# 6.net
KiCad netlist of a schematic drawn in Altium Designer
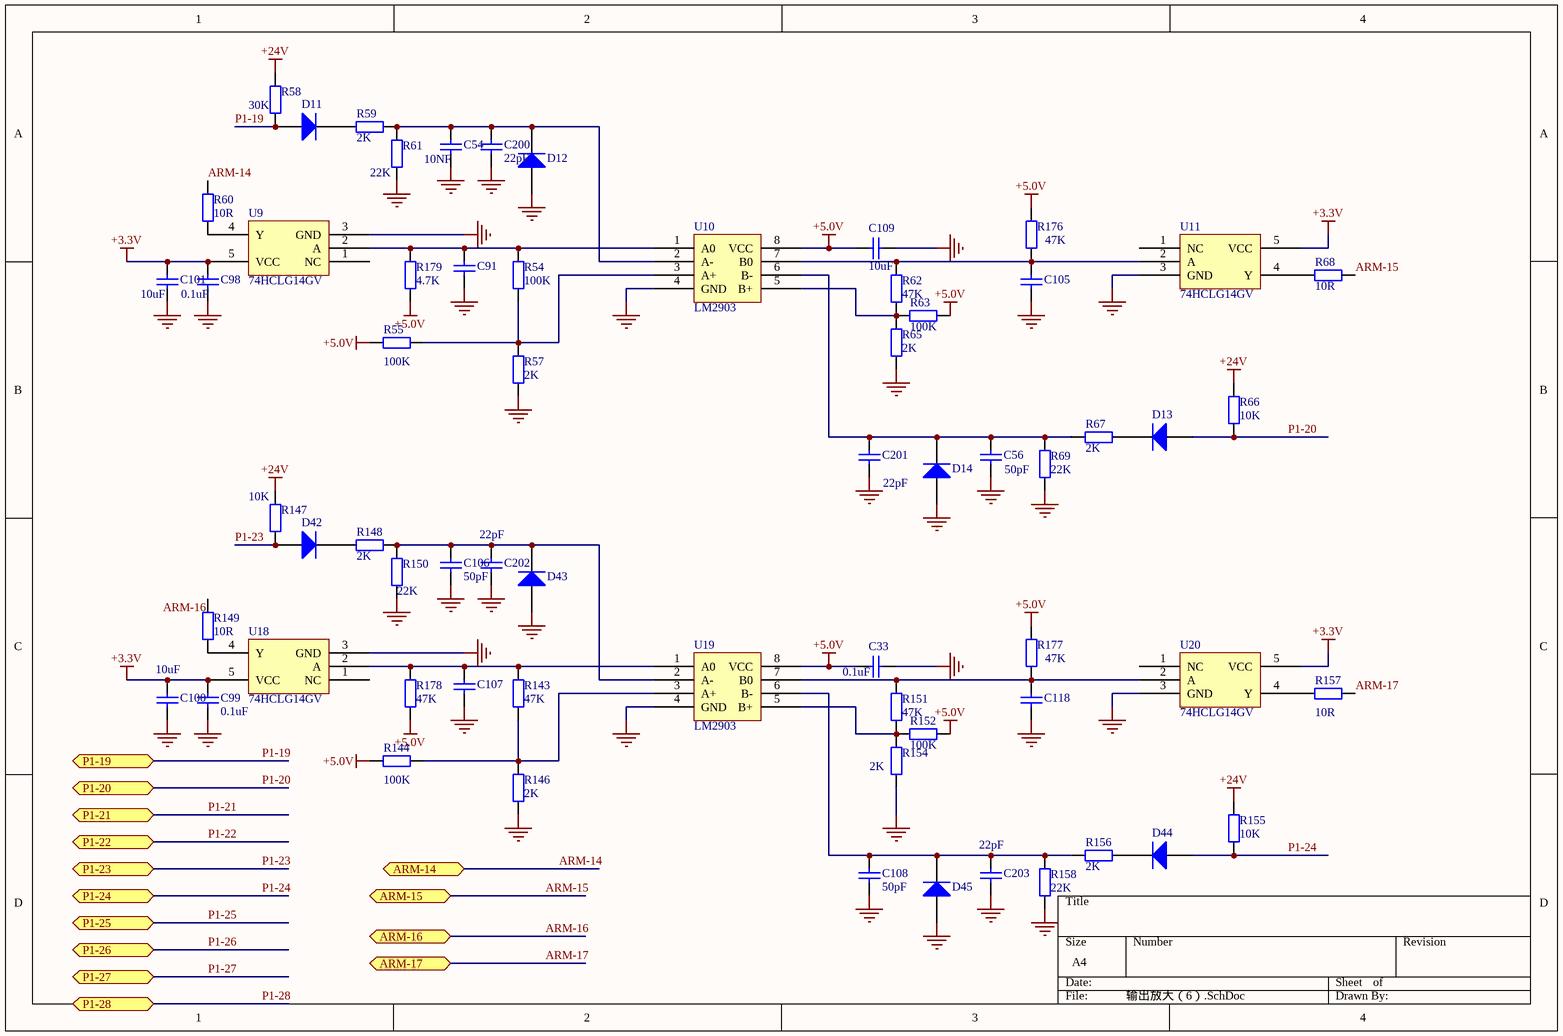
[diagram p0: 输出放大（6）.SchDoc]

(export (version "E")
  (design (tool "Eeschema 10.0.6"))
  (components
    (comp (ref "C33")
      (value "0.1uF")
      (footprint "采集板3.0增加1路模拟量2:C0805")
      (description "Capacitor")
      (fields (field (name "Comment") "Cap") (field (name "PUBLISHER") "Altium Limited"))
      (libsource (lib "Miscellaneous Devices") (part "Cap"))
    )
    (comp (ref "C54")
      (value "10NF")
      (footprint "C0805")
      (description "Capacitor")
      (fields (field (name "Comment") "Cap") (field (name "PUBLISHER") "Altium Limited"))
      (libsource (lib "Miscellaneous Devices") (part "Cap"))
    )
    (comp (ref "C56")
      (value "50pF")
      (footprint "C0805")
      (description "Capacitor")
      (fields (field (name "Comment") "Cap") (field (name "PUBLISHER") "Altium Limited"))
      (libsource (lib "Miscellaneous Devices") (part "Cap"))
    )
    (comp (ref "C91")
      (value "Cap")
      (footprint "C0805")
      (description "Capacitor")
      (fields (field (name "PUBLISHER") "Altium Limited"))
      (libsource (lib "Miscellaneous Devices") (part "Cap"))
    )
    (comp (ref "C98")
      (value "0.1uF")
      (footprint "采集板3.0增加1路模拟量2:C0805")
      (description "Capacitor")
      (fields (field (name "Comment") "Cap") (field (name "PUBLISHER") "Altium Limited"))
      (libsource (lib "Miscellaneous Devices") (part "Cap"))
    )
    (comp (ref "C99")
      (value "0.1uF")
      (footprint "采集板3.0增加1路模拟量2:C0805")
      (description "Capacitor")
      (fields (field (name "Comment") "Cap") (field (name "PUBLISHER") "Altium Limited"))
      (libsource (lib "Miscellaneous Devices") (part "Cap"))
    )
    (comp (ref "C100")
      (value "10uF")
      (footprint "C1206")
      (description "Capacitor")
      (fields (field (name "Comment") "Cap") (field (name "PUBLISHER") "Altium Limited"))
      (libsource (lib "Miscellaneous Devices") (part "Cap"))
    )
    (comp (ref "C101")
      (value "10uF")
      (footprint "C1206")
      (description "Capacitor")
      (fields (field (name "Comment") "Cap") (field (name "PUBLISHER") "Altium Limited"))
      (libsource (lib "Miscellaneous Devices") (part "Cap"))
    )
    (comp (ref "C105")
      (value "Cap")
      (footprint "C0805")
      (description "Capacitor")
      (fields (field (name "PUBLISHER") "Altium Limited"))
      (libsource (lib "Miscellaneous Devices") (part "Cap"))
    )
    (comp (ref "C106")
      (value "50pF")
      (footprint "C0805")
      (description "Capacitor")
      (fields (field (name "Comment") "Cap") (field (name "PUBLISHER") "Altium Limited"))
      (libsource (lib "Miscellaneous Devices") (part "Cap"))
    )
    (comp (ref "C107")
      (value "Cap")
      (footprint "C0805")
      (description "Capacitor")
      (fields (field (name "PUBLISHER") "Altium Limited"))
      (libsource (lib "Miscellaneous Devices") (part "Cap"))
    )
    (comp (ref "C108")
      (value "50pF")
      (footprint "C0805")
      (description "Capacitor")
      (fields (field (name "Comment") "Cap") (field (name "PUBLISHER") "Altium Limited"))
      (libsource (lib "Miscellaneous Devices") (part "Cap"))
    )
    (comp (ref "C109")
      (value "10uF")
      (footprint "C1206")
      (description "Capacitor")
      (fields (field (name "Comment") "Cap") (field (name "PUBLISHER") "Altium Limited"))
      (libsource (lib "Miscellaneous Devices") (part "Cap"))
    )
    (comp (ref "C118")
      (value "Cap")
      (footprint "C0805")
      (description "Capacitor")
      (fields (field (name "PUBLISHER") "Altium Limited"))
      (libsource (lib "Miscellaneous Devices") (part "Cap"))
    )
    (comp (ref "C200")
      (value "22pF")
      (footprint "采集板3.0增加1路模拟量2:C0805")
      (description "Capacitor")
      (fields (field (name "Comment") "Cap") (field (name "PUBLISHER") "Altium Limited"))
      (libsource (lib "Miscellaneous Devices") (part "Cap"))
    )
    (comp (ref "C201")
      (value "22pF")
      (footprint "采集板3.0增加1路模拟量2:C0805")
      (description "Capacitor")
      (fields (field (name "Comment") "Cap") (field (name "PUBLISHER") "Altium Limited"))
      (libsource (lib "Miscellaneous Devices") (part "Cap"))
    )
    (comp (ref "C202")
      (value "22pF")
      (footprint "采集板3.0增加1路模拟量2:C0805")
      (description "Capacitor")
      (fields (field (name "Comment") "Cap") (field (name "PUBLISHER") "Altium Limited"))
      (libsource (lib "Miscellaneous Devices") (part "Cap"))
    )
    (comp (ref "C203")
      (value "22pF")
      (footprint "采集板3.0增加1路模拟量2:C0805")
      (description "Capacitor")
      (fields (field (name "Comment") "Cap") (field (name "PUBLISHER") "Altium Limited"))
      (libsource (lib "Miscellaneous Devices") (part "Cap"))
    )
    (comp (ref "D11")
      (value "Diode 1N4007")
      (footprint "SOD123")
      (description "1 Amp General Purpose Rectifier")
      (fields (field (name "PUBLISHER") "Altium Limited"))
      (libsource (lib "Miscellaneous Devices") (part "Diode 1N4007"))
    )
    (comp (ref "D12")
      (value "Diode 1N4007")
      (footprint "SOD123")
      (description "1 Amp General Purpose Rectifier")
      (fields (field (name "PUBLISHER") "Altium Limited"))
      (libsource (lib "Miscellaneous Devices") (part "Diode 1N4007"))
    )
    (comp (ref "D13")
      (value "Diode 1N4007")
      (footprint "SOD123")
      (description "1 Amp General Purpose Rectifier")
      (fields (field (name "PUBLISHER") "Altium Limited"))
      (libsource (lib "Miscellaneous Devices") (part "Diode 1N4007"))
    )
    (comp (ref "D14")
      (value "Diode 1N4007")
      (footprint "SOD123")
      (description "1 Amp General Purpose Rectifier")
      (fields (field (name "PUBLISHER") "Altium Limited"))
      (libsource (lib "Miscellaneous Devices") (part "Diode 1N4007"))
    )
    (comp (ref "D42")
      (value "Diode 1N4007")
      (footprint "SOD123")
      (description "1 Amp General Purpose Rectifier")
      (fields (field (name "PUBLISHER") "Altium Limited"))
      (libsource (lib "Miscellaneous Devices") (part "Diode 1N4007"))
    )
    (comp (ref "D43")
      (value "Diode 1N4007")
      (footprint "SOD123")
      (description "1 Amp General Purpose Rectifier")
      (fields (field (name "PUBLISHER") "Altium Limited"))
      (libsource (lib "Miscellaneous Devices") (part "Diode 1N4007"))
    )
    (comp (ref "D44")
      (value "Diode 1N4007")
      (footprint "SOD123")
      (description "1 Amp General Purpose Rectifier")
      (fields (field (name "PUBLISHER") "Altium Limited"))
      (libsource (lib "Miscellaneous Devices") (part "Diode 1N4007"))
    )
    (comp (ref "D45")
      (value "Diode 1N4007")
      (footprint "SOD123")
      (description "1 Amp General Purpose Rectifier")
      (fields (field (name "PUBLISHER") "Altium Limited"))
      (libsource (lib "Miscellaneous Devices") (part "Diode 1N4007"))
    )
    (comp (ref "R54")
      (value "100K")
      (footprint "采集板3.0增加1路模拟量2:R0805")
      (description "Resistor")
      (fields (field (name "Comment") "Res2") (field (name "PUBLISHER") "Altium Limited"))
      (libsource (lib "") (part "Res2_3"))
    )
    (comp (ref "R55")
      (value "100K")
      (footprint "采集板3.0增加1路模拟量2:R0805")
      (description "Resistor")
      (fields (field (name "Comment") "Res2") (field (name "PUBLISHER") "Altium Limited"))
      (libsource (lib "") (part "Res2_1"))
    )
    (comp (ref "R57")
      (value "2K")
      (footprint "采集板3.0增加1路模拟量2:R0805")
      (description "Resistor")
      (fields (field (name "Comment") "Res2") (field (name "PUBLISHER") "Altium Limited"))
      (libsource (lib "") (part "Res2_2"))
    )
    (comp (ref "R58")
      (value "30K")
      (footprint "采集板3.0增加1路模拟量2:R0805")
      (description "Resistor")
      (fields (field (name "Comment") "Res2") (field (name "PUBLISHER") "Altium Limited"))
      (libsource (lib "") (part "Res2_2"))
    )
    (comp (ref "R59")
      (value "2K")
      (footprint "采集板3.0增加1路模拟量2:R0805")
      (description "Resistor")
      (fields (field (name "Comment") "Res2") (field (name "PUBLISHER") "Altium Limited"))
      (libsource (lib "Miscellaneous Devices") (part "Res2"))
    )
    (comp (ref "R60")
      (value "10R")
      (footprint "采集板3.0增加1路模拟量2:R0805")
      (description "Resistor")
      (fields (field (name "Comment") "Res2") (field (name "PUBLISHER") "Altium Limited"))
      (libsource (lib "") (part "Res2_3"))
    )
    (comp (ref "R61")
      (value "22K")
      (footprint "采集板3.0增加1路模拟量2:R0805")
      (description "Resistor")
      (fields (field (name "Comment") "Res2") (field (name "PUBLISHER") "Altium Limited"))
      (libsource (lib "") (part "Res2_2"))
    )
    (comp (ref "R62")
      (value "47K")
      (footprint "采集板3.0增加1路模拟量2:R0805")
      (description "Resistor")
      (fields (field (name "Comment") "Res2") (field (name "PUBLISHER") "Altium Limited"))
      (libsource (lib "") (part "Res2_2"))
    )
    (comp (ref "R63")
      (value "100K")
      (footprint "采集板3.0增加1路模拟量2:R0805")
      (description "Resistor")
      (fields (field (name "Comment") "Res2") (field (name "PUBLISHER") "Altium Limited"))
      (libsource (lib "Miscellaneous Devices") (part "Res2"))
    )
    (comp (ref "R65")
      (value "2K")
      (footprint "采集板3.0增加1路模拟量2:R0805")
      (description "Resistor")
      (fields (field (name "Comment") "Res2") (field (name "PUBLISHER") "Altium Limited"))
      (libsource (lib "") (part "Res2_2"))
    )
    (comp (ref "R66")
      (value "10K")
      (footprint "采集板3.0增加1路模拟量2:R0805")
      (description "Resistor")
      (fields (field (name "Comment") "Res2") (field (name "PUBLISHER") "Altium Limited"))
      (libsource (lib "") (part "Res2_3"))
    )
    (comp (ref "R67")
      (value "2K")
      (footprint "采集板3.0增加1路模拟量2:R0805")
      (description "Resistor")
      (fields (field (name "Comment") "Res2") (field (name "PUBLISHER") "Altium Limited"))
      (libsource (lib "Miscellaneous Devices") (part "Res2"))
    )
    (comp (ref "R68")
      (value "10R")
      (footprint "采集板3.0增加1路模拟量2:R0805")
      (description "Resistor")
      (fields (field (name "Comment") "Res2") (field (name "PUBLISHER") "Altium Limited"))
      (libsource (lib "") (part "Res2_1"))
    )
    (comp (ref "R69")
      (value "22K")
      (footprint "采集板3.0增加1路模拟量2:R0805")
      (description "Resistor")
      (fields (field (name "Comment") "Res2") (field (name "PUBLISHER") "Altium Limited"))
      (libsource (lib "") (part "Res2_3"))
    )
    (comp (ref "R143")
      (value "47K")
      (footprint "采集板3.0增加1路模拟量2:R0805")
      (description "Resistor")
      (fields (field (name "Comment") "Res2") (field (name "PUBLISHER") "Altium Limited"))
      (libsource (lib "") (part "Res2_3"))
    )
    (comp (ref "R144")
      (value "100K")
      (footprint "采集板3.0增加1路模拟量2:R0805")
      (description "Resistor")
      (fields (field (name "Comment") "Res2") (field (name "PUBLISHER") "Altium Limited"))
      (libsource (lib "") (part "Res2_1"))
    )
    (comp (ref "R146")
      (value "2K")
      (footprint "采集板3.0增加1路模拟量2:R0805")
      (description "Resistor")
      (fields (field (name "Comment") "Res2") (field (name "PUBLISHER") "Altium Limited"))
      (libsource (lib "") (part "Res2_2"))
    )
    (comp (ref "R147")
      (value "10K")
      (footprint "采集板3.0增加1路模拟量2:R0805")
      (description "Resistor")
      (fields (field (name "Comment") "Res2") (field (name "PUBLISHER") "Altium Limited"))
      (libsource (lib "") (part "Res2_2"))
    )
    (comp (ref "R148")
      (value "2K")
      (footprint "采集板3.0增加1路模拟量2:R0805")
      (description "Resistor")
      (fields (field (name "Comment") "Res2") (field (name "PUBLISHER") "Altium Limited"))
      (libsource (lib "Miscellaneous Devices") (part "Res2"))
    )
    (comp (ref "R149")
      (value "10R")
      (footprint "采集板3.0增加1路模拟量2:R0805")
      (description "Resistor")
      (fields (field (name "Comment") "Res2") (field (name "PUBLISHER") "Altium Limited"))
      (libsource (lib "") (part "Res2_3"))
    )
    (comp (ref "R150")
      (value "22K")
      (footprint "采集板3.0增加1路模拟量2:R0805")
      (description "Resistor")
      (fields (field (name "Comment") "Res2") (field (name "PUBLISHER") "Altium Limited"))
      (libsource (lib "") (part "Res2_2"))
    )
    (comp (ref "R151")
      (value "47K")
      (footprint "采集板3.0增加1路模拟量2:R0805")
      (description "Resistor")
      (fields (field (name "Comment") "Res2") (field (name "PUBLISHER") "Altium Limited"))
      (libsource (lib "") (part "Res2_2"))
    )
    (comp (ref "R152")
      (value "100K")
      (footprint "采集板3.0增加1路模拟量2:R0805")
      (description "Resistor")
      (fields (field (name "Comment") "Res2") (field (name "PUBLISHER") "Altium Limited"))
      (libsource (lib "Miscellaneous Devices") (part "Res2"))
    )
    (comp (ref "R154")
      (value "2K")
      (footprint "采集板3.0增加1路模拟量2:R0805")
      (description "Resistor")
      (fields (field (name "Comment") "Res2") (field (name "PUBLISHER") "Altium Limited"))
      (libsource (lib "") (part "Res2_3"))
    )
    (comp (ref "R155")
      (value "10K")
      (footprint "采集板3.0增加1路模拟量2:R0805")
      (description "Resistor")
      (fields (field (name "Comment") "Res2") (field (name "PUBLISHER") "Altium Limited"))
      (libsource (lib "") (part "Res2_3"))
    )
    (comp (ref "R156")
      (value "2K")
      (footprint "采集板3.0增加1路模拟量2:R0805")
      (description "Resistor")
      (fields (field (name "Comment") "Res2") (field (name "PUBLISHER") "Altium Limited"))
      (libsource (lib "Miscellaneous Devices") (part "Res2"))
    )
    (comp (ref "R157")
      (value "10R")
      (footprint "采集板3.0增加1路模拟量2:R0805")
      (description "Resistor")
      (fields (field (name "Comment") "Res2") (field (name "PUBLISHER") "Altium Limited"))
      (libsource (lib "Miscellaneous Devices") (part "Res2"))
    )
    (comp (ref "R158")
      (value "22K")
      (footprint "采集板3.0增加1路模拟量2:R0805")
      (description "Resistor")
      (fields (field (name "Comment") "Res2") (field (name "PUBLISHER") "Altium Limited"))
      (libsource (lib "") (part "Res2_3"))
    )
    (comp (ref "R176")
      (value "47K")
      (footprint "采集板3.0增加1路模拟量2:R0805")
      (description "Resistor")
      (fields (field (name "Comment") "Res2") (field (name "PUBLISHER") "Altium Limited"))
      (libsource (lib "") (part "Res2_3"))
    )
    (comp (ref "R177")
      (value "47K")
      (footprint "采集板3.0增加1路模拟量2:R0805")
      (description "Resistor")
      (fields (field (name "Comment") "Res2") (field (name "PUBLISHER") "Altium Limited"))
      (libsource (lib "") (part "Res2_3"))
    )
    (comp (ref "R178")
      (value "47K")
      (footprint "采集板3.0增加1路模拟量2:R0805")
      (description "Resistor")
      (fields (field (name "Comment") "Res2") (field (name "PUBLISHER") "Altium Limited"))
      (libsource (lib "") (part "Res2_2"))
    )
    (comp (ref "R179")
      (value "4.7K")
      (footprint "采集板3.0增加1路模拟量2:R0805")
      (description "Resistor")
      (fields (field (name "Comment") "Res2") (field (name "PUBLISHER") "Altium Limited"))
      (libsource (lib "") (part "Res2_2"))
    )
    (comp (ref "U9") (value "74HCLG14GV") (footprint "SOT23-5") (libsource (lib "") (part "Component_1_1")))
    (comp (ref "U10") (value "LM2903") (footprint "SO-8") (libsource (lib "LM2903") (part "Component_1")))
    (comp (ref "U11")
      (value "74HCLG14GV")
      (footprint "SOT23-5")
      (libsource (lib "Schlib1") (part "Component_1"))
    )
    (comp (ref "U18") (value "74HCLG14GV") (footprint "SOT23-5") (libsource (lib "") (part "Component_1_1")))
    (comp (ref "U19") (value "LM2903") (footprint "SO-8") (libsource (lib "LM2903") (part "Component_1")))
    (comp (ref "U20")
      (value "74HCLG14GV")
      (footprint "SOT23-5")
      (libsource (lib "Schlib1") (part "Component_1"))
    )
  )
  (nets
    (net (code "1") (name "+3.3V") (class "Default")
      (node (ref "C100") (pin "2") (pinfunction "2_2") (pintype "passive"))
      (node (ref "C101") (pin "2") (pinfunction "2_2") (pintype "passive"))
      (node (ref "C98") (pin "2") (pinfunction "2_2") (pintype "passive"))
      (node (ref "C99") (pin "1") (pinfunction "1_1") (pintype "passive"))
      (node (ref "U11") (pin "5") (pinfunction "VCC_5") (pintype "passive"))
      (node (ref "U18") (pin "5") (pinfunction "VCC_5") (pintype "passive"))
      (node (ref "U20") (pin "5") (pinfunction "VCC_5") (pintype "passive"))
      (node (ref "U9") (pin "5") (pinfunction "VCC_5") (pintype "passive"))
    )
    (net (code "2") (name "+5.0V") (class "Default")
      (node (ref "C109") (pin "1") (pinfunction "1_1") (pintype "passive"))
      (node (ref "C33") (pin "2") (pinfunction "2_2") (pintype "passive"))
      (node (ref "R144") (pin "2") (pinfunction "2_2") (pintype "passive"))
      (node (ref "R152") (pin "2") (pinfunction "2_2") (pintype "passive"))
      (node (ref "R176") (pin "1") (pinfunction "1_1") (pintype "passive"))
      (node (ref "R177") (pin "1") (pinfunction "1_1") (pintype "passive"))
      (node (ref "R178") (pin "1") (pinfunction "1_1") (pintype "passive"))
      (node (ref "R179") (pin "1") (pinfunction "1_1") (pintype "passive"))
      (node (ref "R55") (pin "2") (pinfunction "2_2") (pintype "passive"))
      (node (ref "R63") (pin "2") (pinfunction "2_2") (pintype "passive"))
      (node (ref "U10") (pin "8") (pinfunction "VCC_8") (pintype "passive"))
      (node (ref "U19") (pin "8") (pinfunction "VCC_8") (pintype "passive"))
    )
    (net (code "3") (name "+24V") (class "Default")
      (node (ref "R147") (pin "2") (pinfunction "2_2") (pintype "passive"))
      (node (ref "R155") (pin "1") (pinfunction "1_1") (pintype "passive"))
      (node (ref "R58") (pin "2") (pinfunction "2_2") (pintype "passive"))
      (node (ref "R66") (pin "1") (pinfunction "1_1") (pintype "passive"))
    )
    (net (code "4") (name "/ARM-14") (class "Default")
      (node (ref "R60") (pin "1") (pinfunction "1_1") (pintype "passive"))
    )
    (net (code "5") (name "/ARM-15") (class "Default")
      (node (ref "R68") (pin "1") (pinfunction "1_1") (pintype "passive"))
    )
    (net (code "6") (name "/ARM-16") (class "Default")
      (node (ref "R149") (pin "1") (pinfunction "1_1") (pintype "passive"))
    )
    (net (code "7") (name "/ARM-17") (class "Default")
      (node (ref "R157") (pin "2") (pinfunction "2_2") (pintype "passive"))
    )
    (net (code "8") (name "/P1-19") (class "Default")
      (node (ref "D11") (pin "1") (pinfunction "A_1") (pintype "passive"))
      (node (ref "R58") (pin "1") (pinfunction "1_1") (pintype "passive"))
    )
    (net (code "9") (name "/P1-20") (class "Default")
      (node (ref "D13") (pin "1") (pinfunction "A_1") (pintype "passive"))
      (node (ref "R66") (pin "2") (pinfunction "2_2") (pintype "passive"))
    )
    (net (code "12") (name "/P1-23") (class "Default")
      (node (ref "D42") (pin "1") (pinfunction "A_1") (pintype "passive"))
      (node (ref "R147") (pin "1") (pinfunction "1_1") (pintype "passive"))
    )
    (net (code "13") (name "/P1-24") (class "Default")
      (node (ref "D44") (pin "1") (pinfunction "A_1") (pintype "passive"))
      (node (ref "R155") (pin "2") (pinfunction "2_2") (pintype "passive"))
    )
    (net (code "18") (name "GND") (class "Default")
      (node (ref "C100") (pin "1") (pinfunction "1_1") (pintype "passive"))
      (node (ref "C101") (pin "1") (pinfunction "1_1") (pintype "passive"))
      (node (ref "C105") (pin "2") (pinfunction "2_2") (pintype "passive"))
      (node (ref "C106") (pin "2") (pinfunction "2_2") (pintype "passive"))
      (node (ref "C107") (pin "1") (pinfunction "1_1") (pintype "passive"))
      (node (ref "C108") (pin "1") (pinfunction "1_1") (pintype "passive"))
      (node (ref "C109") (pin "2") (pinfunction "2_2") (pintype "passive"))
      (node (ref "C118") (pin "1") (pinfunction "1_1") (pintype "passive"))
      (node (ref "C200") (pin "2") (pinfunction "2_2") (pintype "passive"))
      (node (ref "C201") (pin "2") (pinfunction "2_2") (pintype "passive"))
      (node (ref "C202") (pin "1") (pinfunction "1_1") (pintype "passive"))
      (node (ref "C203") (pin "2") (pinfunction "2_2") (pintype "passive"))
      (node (ref "C33") (pin "1") (pinfunction "1_1") (pintype "passive"))
      (node (ref "C54") (pin "1") (pinfunction "1_1") (pintype "passive"))
      (node (ref "C56") (pin "2") (pinfunction "2_2") (pintype "passive"))
      (node (ref "C91") (pin "2") (pinfunction "2_2") (pintype "passive"))
      (node (ref "C98") (pin "1") (pinfunction "1_1") (pintype "passive"))
      (node (ref "C99") (pin "2") (pinfunction "2_2") (pintype "passive"))
      (node (ref "D12") (pin "1") (pinfunction "A_1") (pintype "passive"))
      (node (ref "D14") (pin "1") (pinfunction "A_1") (pintype "passive"))
      (node (ref "D43") (pin "1") (pinfunction "A_1") (pintype "passive"))
      (node (ref "D45") (pin "1") (pinfunction "A_1") (pintype "passive"))
      (node (ref "R146") (pin "1") (pinfunction "1_1") (pintype "passive"))
      (node (ref "R150") (pin "1") (pinfunction "1_1") (pintype "passive"))
      (node (ref "R154") (pin "2") (pinfunction "2_2") (pintype "passive"))
      (node (ref "R158") (pin "2") (pinfunction "2_2") (pintype "passive"))
      (node (ref "R57") (pin "1") (pinfunction "1_1") (pintype "passive"))
      (node (ref "R61") (pin "1") (pinfunction "1_1") (pintype "passive"))
      (node (ref "R65") (pin "1") (pinfunction "1_1") (pintype "passive"))
      (node (ref "R69") (pin "2") (pinfunction "2_2") (pintype "passive"))
      (node (ref "U10") (pin "4") (pinfunction "GND_4") (pintype "passive"))
      (node (ref "U11") (pin "3") (pinfunction "GND_3") (pintype "passive"))
      (node (ref "U18") (pin "3") (pinfunction "GND_3") (pintype "passive"))
      (node (ref "U19") (pin "4") (pinfunction "GND_4") (pintype "passive"))
      (node (ref "U20") (pin "3") (pinfunction "GND_3") (pintype "passive"))
      (node (ref "U9") (pin "3") (pinfunction "GND_3") (pintype "passive"))
    )
    (net (code "19") (name "Net-(D11-K)") (class "Default")
      (node (ref "D11") (pin "2") (pinfunction "K_2") (pintype "passive"))
      (node (ref "R59") (pin "1") (pinfunction "1_1") (pintype "passive"))
    )
    (net (code "20") (name "Net-(D12-K)") (class "Default")
      (node (ref "C200") (pin "1") (pinfunction "1_1") (pintype "passive"))
      (node (ref "C54") (pin "2") (pinfunction "2_2") (pintype "passive"))
      (node (ref "D12") (pin "2") (pinfunction "K_2") (pintype "passive"))
      (node (ref "R59") (pin "2") (pinfunction "2_2") (pintype "passive"))
      (node (ref "R61") (pin "2") (pinfunction "2_2") (pintype "passive"))
      (node (ref "U10") (pin "2") (pinfunction "A-_2") (pintype "passive"))
    )
    (net (code "21") (name "Net-(D13-K)") (class "Default")
      (node (ref "D13") (pin "2") (pinfunction "K_2") (pintype "passive"))
      (node (ref "R67") (pin "2") (pinfunction "2_2") (pintype "passive"))
    )
    (net (code "22") (name "Net-(D14-K)") (class "Default")
      (node (ref "C201") (pin "1") (pinfunction "1_1") (pintype "passive"))
      (node (ref "C56") (pin "1") (pinfunction "1_1") (pintype "passive"))
      (node (ref "D14") (pin "2") (pinfunction "K_2") (pintype "passive"))
      (node (ref "R67") (pin "1") (pinfunction "1_1") (pintype "passive"))
      (node (ref "R69") (pin "1") (pinfunction "1_1") (pintype "passive"))
      (node (ref "U10") (pin "6") (pinfunction "B-_6") (pintype "passive"))
    )
    (net (code "23") (name "Net-(D42-K)") (class "Default")
      (node (ref "D42") (pin "2") (pinfunction "K_2") (pintype "passive"))
      (node (ref "R148") (pin "1") (pinfunction "1_1") (pintype "passive"))
    )
    (net (code "24") (name "Net-(D43-K)") (class "Default")
      (node (ref "C106") (pin "1") (pinfunction "1_1") (pintype "passive"))
      (node (ref "C202") (pin "2") (pinfunction "2_2") (pintype "passive"))
      (node (ref "D43") (pin "2") (pinfunction "K_2") (pintype "passive"))
      (node (ref "R148") (pin "2") (pinfunction "2_2") (pintype "passive"))
      (node (ref "R150") (pin "2") (pinfunction "2_2") (pintype "passive"))
      (node (ref "U19") (pin "2") (pinfunction "A-_2") (pintype "passive"))
    )
    (net (code "25") (name "Net-(D44-K)") (class "Default")
      (node (ref "D44") (pin "2") (pinfunction "K_2") (pintype "passive"))
      (node (ref "R156") (pin "2") (pinfunction "2_2") (pintype "passive"))
    )
    (net (code "26") (name "Net-(D45-K)") (class "Default")
      (node (ref "C108") (pin "2") (pinfunction "2_2") (pintype "passive"))
      (node (ref "C203") (pin "1") (pinfunction "1_1") (pintype "passive"))
      (node (ref "D45") (pin "2") (pinfunction "K_2") (pintype "passive"))
      (node (ref "R156") (pin "1") (pinfunction "1_1") (pintype "passive"))
      (node (ref "R158") (pin "1") (pinfunction "1_1") (pintype "passive"))
      (node (ref "U19") (pin "6") (pinfunction "B-_6") (pintype "passive"))
    )
    (net (code "27") (name "Net-(U9-Y)") (class "Default")
      (node (ref "R60") (pin "2") (pinfunction "2_2") (pintype "passive"))
      (node (ref "U9") (pin "4") (pinfunction "Y_4") (pintype "passive"))
    )
    (net (code "28") (name "Net-(U10-A+)") (class "Default")
      (node (ref "R54") (pin "2") (pinfunction "2_2") (pintype "passive"))
      (node (ref "R55") (pin "1") (pinfunction "1_1") (pintype "passive"))
      (node (ref "R57") (pin "2") (pinfunction "2_2") (pintype "passive"))
      (node (ref "U10") (pin "3") (pinfunction "A+_3") (pintype "passive"))
    )
    (net (code "29") (name "Net-(U10-A0)") (class "Default")
      (node (ref "C91") (pin "1") (pinfunction "1_1") (pintype "passive"))
      (node (ref "R179") (pin "2") (pinfunction "2_2") (pintype "passive"))
      (node (ref "R54") (pin "1") (pinfunction "1_1") (pintype "passive"))
      (node (ref "U10") (pin "1") (pinfunction "A0_1") (pintype "passive"))
      (node (ref "U9") (pin "2") (pinfunction "A_2") (pintype "passive"))
    )
    (net (code "30") (name "Net-(U10-B+)") (class "Default")
      (node (ref "R62") (pin "1") (pinfunction "1_1") (pintype "passive"))
      (node (ref "R63") (pin "1") (pinfunction "1_1") (pintype "passive"))
      (node (ref "R65") (pin "2") (pinfunction "2_2") (pintype "passive"))
      (node (ref "U10") (pin "5") (pinfunction "B+_5") (pintype "passive"))
    )
    (net (code "31") (name "Net-(U10-B0)") (class "Default")
      (node (ref "C105") (pin "1") (pinfunction "1_1") (pintype "passive"))
      (node (ref "R176") (pin "2") (pinfunction "2_2") (pintype "passive"))
      (node (ref "R62") (pin "2") (pinfunction "2_2") (pintype "passive"))
      (node (ref "U10") (pin "7") (pinfunction "B0_7") (pintype "passive"))
      (node (ref "U11") (pin "2") (pinfunction "A_2") (pintype "passive"))
    )
    (net (code "32") (name "Net-(U11-Y)") (class "Default")
      (node (ref "R68") (pin "2") (pinfunction "2_2") (pintype "passive"))
      (node (ref "U11") (pin "4") (pinfunction "Y_4") (pintype "passive"))
    )
    (net (code "33") (name "Net-(U18-A)") (class "Default")
      (node (ref "C107") (pin "2") (pinfunction "2_2") (pintype "passive"))
      (node (ref "R143") (pin "1") (pinfunction "1_1") (pintype "passive"))
      (node (ref "R178") (pin "2") (pinfunction "2_2") (pintype "passive"))
      (node (ref "U18") (pin "2") (pinfunction "A_2") (pintype "passive"))
      (node (ref "U19") (pin "1") (pinfunction "A0_1") (pintype "passive"))
    )
    (net (code "34") (name "Net-(U18-Y)") (class "Default")
      (node (ref "R149") (pin "2") (pinfunction "2_2") (pintype "passive"))
      (node (ref "U18") (pin "4") (pinfunction "Y_4") (pintype "passive"))
    )
    (net (code "35") (name "Net-(U19-A+)") (class "Default")
      (node (ref "R143") (pin "2") (pinfunction "2_2") (pintype "passive"))
      (node (ref "R144") (pin "1") (pinfunction "1_1") (pintype "passive"))
      (node (ref "R146") (pin "2") (pinfunction "2_2") (pintype "passive"))
      (node (ref "U19") (pin "3") (pinfunction "A+_3") (pintype "passive"))
    )
    (net (code "36") (name "Net-(U19-B+)") (class "Default")
      (node (ref "R151") (pin "1") (pinfunction "1_1") (pintype "passive"))
      (node (ref "R152") (pin "1") (pinfunction "1_1") (pintype "passive"))
      (node (ref "R154") (pin "1") (pinfunction "1_1") (pintype "passive"))
      (node (ref "U19") (pin "5") (pinfunction "B+_5") (pintype "passive"))
    )
    (net (code "37") (name "Net-(U19-B0)") (class "Default")
      (node (ref "C118") (pin "2") (pinfunction "2_2") (pintype "passive"))
      (node (ref "R151") (pin "2") (pinfunction "2_2") (pintype "passive"))
      (node (ref "R177") (pin "2") (pinfunction "2_2") (pintype "passive"))
      (node (ref "U19") (pin "7") (pinfunction "B0_7") (pintype "passive"))
      (node (ref "U20") (pin "2") (pinfunction "A_2") (pintype "passive"))
    )
    (net (code "38") (name "Net-(U20-Y)") (class "Default")
      (node (ref "R157") (pin "1") (pinfunction "1_1") (pintype "passive"))
      (node (ref "U20") (pin "4") (pinfunction "Y_4") (pintype "passive"))
    )
    (net (code "39") (name "unconnected-(U9-NC-Pad1)") (class "Default")
      (node (ref "U9") (pin "1") (pinfunction "NC_1") (pintype "passive"))
    )
    (net (code "40") (name "unconnected-(U11-NC-Pad1)") (class "Default")
      (node (ref "U11") (pin "1") (pinfunction "NC_1") (pintype "passive"))
    )
    (net (code "41") (name "unconnected-(U18-NC-Pad1)") (class "Default")
      (node (ref "U18") (pin "1") (pinfunction "NC_1") (pintype "passive"))
    )
    (net (code "42") (name "unconnected-(U20-NC-Pad1)") (class "Default")
      (node (ref "U20") (pin "1") (pinfunction "NC_1") (pintype "passive"))
    )
  )
)
